# Sheet1.net
KiCad netlist of a schematic drawn in Altium Designer
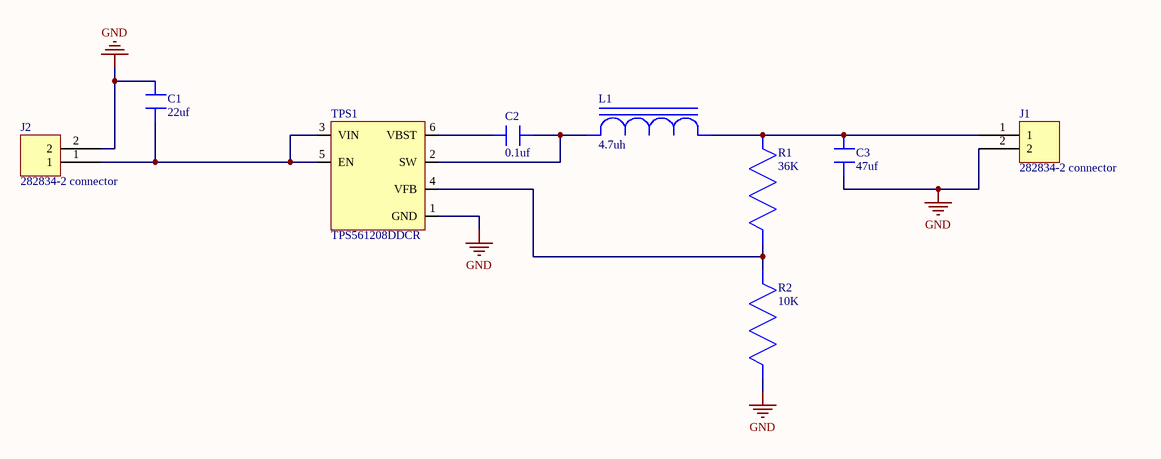
[diagram p0: Sheet1.SchDoc]

(export (version "E")
  (design (tool "Eeschema 10.0.6"))
  (components
    (comp (ref "C1")
      (value "22uf")
      (footprint "Capacitor 22uf 10v")
      (fields
        (field (name "MANUFACTURER") "Samsung")
        (field (name "MANUFACTURER PART NUMBER") "CL10A226MP8ZUNE")
      )
      (libsource (lib "Schlib1") (part "CL10A226MP8ZUNE"))
    )
    (comp (ref "C2")
      (value "0.1uf")
      (footprint "Capacitor 0.1uf 10v")
      (description "Multilayer Ceramic Capacitor, 0.1 uF, 10 V, ± 10%, X5R, 0402 [1005 Metric]")
      (fields
        (field (name "MANUFACTURER") "Samsung")
        (field (name "MANUFACTURER PART NUMBER") "CL05A104KP5NNNC")
      )
      (libsource (lib "Schlib1") (part "CL05A104KP5NNNC"))
    )
    (comp (ref "C3")
      (value "47uf")
      (footprint "Capacitor 47uf")
      (description "Cap Ceramic 47uF 10V X5R 20% SMD 1206 85°C Embossed Plastic T/R")
      (fields
        (field (name "MANUFACTURER") "Samsung")
        (field (name "MANUFACTURER PART NUMBER") "CL31A476MPHNNNE")
      )
      (libsource (lib "Schlib1") (part "CL31A476MPHNNNE"))
    )
    (comp (ref "J1")
      (value "282834-2 connector")
      (footprint "282834-2")
      (description "Conn PC Board Terminal Block Receptacle 2 POS 2.54mm RA Through Hole 10A")
      (fields
        (field (name "MANUFACTURER") "TE Connectivity")
        (field (name "MANUFACTURER PART NUMBER") "282834-2")
      )
      (libsource (lib "Schlib1") (part "282834-2"))
    )
    (comp (ref "J2")
      (value "282834-2 connector")
      (footprint "282834-2")
      (description "Conn PC Board Terminal Block Receptacle 2 POS 2.54mm RA Through Hole 10A")
      (fields
        (field (name "MANUFACTURER") "TE Connectivity")
        (field (name "MANUFACTURER PART NUMBER") "282834-2")
      )
      (libsource (lib "") (part "282834-2_1"))
    )
    (comp (ref "L1")
      (value "4.7uh")
      (footprint "Inductor 4.7uh 1a")
      (description "FIXED IND 4.7UH 1A 216 MOHM SMD")
      (fields
        (field (name "MANUFACTURER") "Taiyo Yuden")
        (field (name "MANUFACTURER PART NUMBER") "BRL3225T4R7M")
      )
      (libsource (lib "Schlib1") (part "BRL3225T4R7M"))
    )
    (comp (ref "R1")
      (value "36K")
      (footprint "Resistor 36K")
      (description "SMD Chip Resistor, 36 kOhm, ± 1%, 125 mW, 0805 [2012 Metric], Thick Film, General Purpose")
      (fields
        (field (name "MANUFACTURER") "Vishay")
        (field (name "MANUFACTURER PART NUMBER") "CRCW080536K0FKEA")
      )
      (libsource (lib "Schlib1") (part "CRCW080536K0FKEA"))
    )
    (comp (ref "R2")
      (value "10K")
      (footprint "Resistor 10k")
      (description "Resistor, Thick Film Chip; 10 K Ohms; Case 0805; 0.125W; +/-1%; SMD; 100ppm/K; 150V")
      (fields
        (field (name "MANUFACTURER") "Vishay Dale")
        (field (name "MANUFACTURER PART NUMBER") "CRCW080510K0FKTA")
      )
      (libsource (lib "Schlib1") (part "CRCW080510K0FKTA"))
    )
    (comp (ref "TPS1")
      (value "TPS561208DDCR")
      (footprint "TPS")
      (description "4.5V to 17V Input, 1A Output, Synchronous Step-Down Converter 6-SOT-23-THIN -40 to 125")
      (fields (field (name "MANUFACTURER") "Texas Instruments"))
      (libsource (lib "Schlib1") (part "TPS561208DDCR"))
    )
  )
  (nets
    (net (code "1") (name "GND") (class "Default")
      (node (ref "C1") (pin "2") (pinfunction "2_2") (pintype "passive"))
      (node (ref "C3") (pin "1") (pinfunction "1_1") (pintype "passive"))
      (node (ref "J1") (pin "2") (pinfunction "2_2") (pintype "passive"))
      (node (ref "J2") (pin "2") (pinfunction "2_2") (pintype "passive"))
      (node (ref "R2") (pin "1") (pinfunction "1_1") (pintype "passive"))
      (node (ref "TPS1") (pin "1") (pinfunction "GND_1") (pintype "passive"))
    )
    (net (code "2") (name "Net-(C3-Pad2)") (class "Default")
      (node (ref "C3") (pin "2") (pinfunction "2_2") (pintype "passive"))
      (node (ref "J1") (pin "1") (pinfunction "1_1") (pintype "passive"))
      (node (ref "L1") (pin "2") (pinfunction "2_2") (pintype "passive"))
      (node (ref "R1") (pin "2") (pinfunction "2_2") (pintype "passive"))
    )
    (net (code "3") (name "Net-(TPS1-EN)") (class "Default")
      (node (ref "C1") (pin "1") (pinfunction "1_1") (pintype "passive"))
      (node (ref "J2") (pin "1") (pinfunction "1_1") (pintype "passive"))
      (node (ref "TPS1") (pin "3") (pinfunction "VIN_3") (pintype "passive"))
      (node (ref "TPS1") (pin "5") (pinfunction "EN_5") (pintype "passive"))
    )
    (net (code "4") (name "Net-(TPS1-SW)") (class "Default")
      (node (ref "C2") (pin "2") (pinfunction "2_2") (pintype "passive"))
      (node (ref "L1") (pin "1") (pinfunction "1_1") (pintype "passive"))
      (node (ref "TPS1") (pin "2") (pinfunction "SW_2") (pintype "passive"))
    )
    (net (code "5") (name "Net-(TPS1-VBST)") (class "Default")
      (node (ref "C2") (pin "1") (pinfunction "1_1") (pintype "passive"))
      (node (ref "TPS1") (pin "6") (pinfunction "VBST_6") (pintype "passive"))
    )
    (net (code "6") (name "Net-(TPS1-VFB)") (class "Default")
      (node (ref "R1") (pin "1") (pinfunction "1_1") (pintype "passive"))
      (node (ref "R2") (pin "2") (pinfunction "2_2") (pintype "passive"))
      (node (ref "TPS1") (pin "4") (pinfunction "VFB_4") (pintype "passive"))
    )
  )
)
